# Debug-UART.net
KiCad netlist of a schematic drawn in Altium Designer
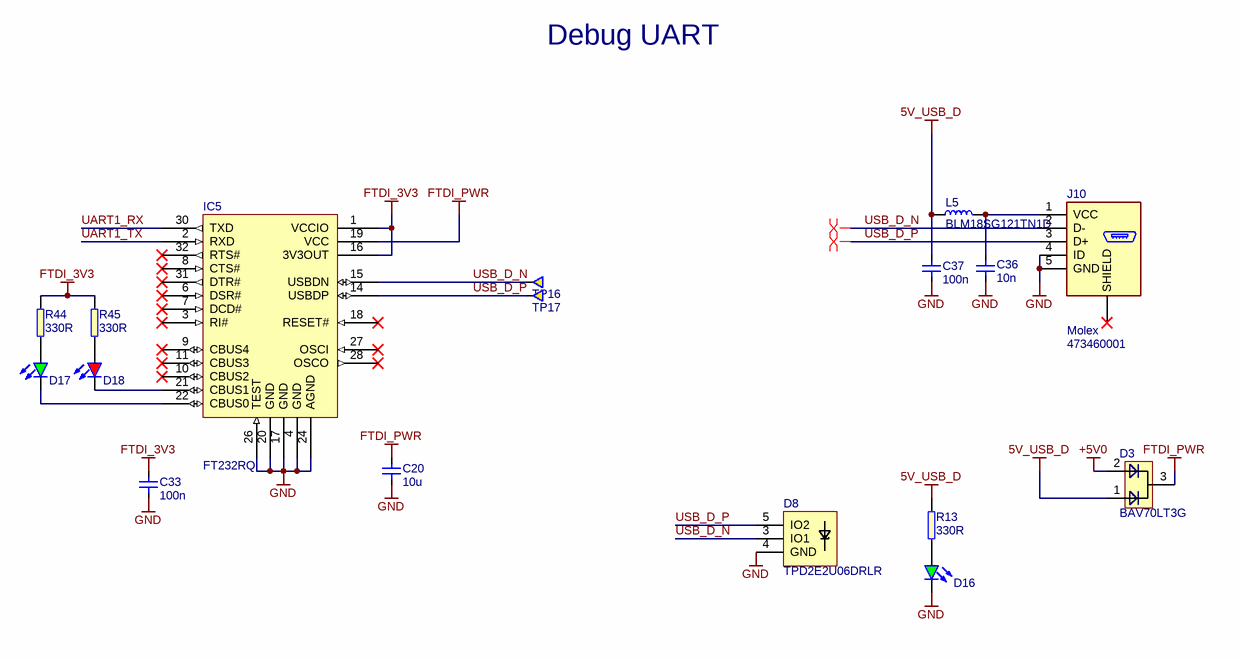
[diagram p0: Debug-UART.SchDoc]

(export (version "E")
  (design (tool "Eeschema 10.0.6"))
  (components
    (comp (ref "C20")
      (value "10u")
      (footprint "0402")
      (description "MLCC SMT Capacitor 10uF 0402")
      (fields (field (name "MANUFACTURER") "TDK") (field (name "PART NUMBER") "C_10u_0402"))
      (libsource (lib "TK1Baseboard") (part "C_10u_0402"))
    )
    (comp (ref "C33")
      (value "100n")
      (footprint "0402")
      (description "MLCC SMT Capacitor 100n 0402")
      (fields (field (name "MANUFACTURER") "TDK") (field (name "PART NUMBER") "C_100n_0402"))
      (libsource (lib "TK1Baseboard") (part "C_100n_0402"))
    )
    (comp (ref "C36")
      (value "10n")
      (footprint "0402")
      (description "MLCC SMT Capacitor 10 nF 0402")
      (fields (field (name "MANUFACTURER") "AVX") (field (name "PART NUMBER") "C_10n_0402"))
      (libsource (lib "TK1Baseboard") (part "C_10n_0402"))
    )
    (comp (ref "C37")
      (value "100n")
      (footprint "0402")
      (description "MLCC SMT Capacitor 100n 0402")
      (fields (field (name "MANUFACTURER") "TDK") (field (name "PART NUMBER") "C_100n_0402"))
      (libsource (lib "TK1Baseboard") (part "C_100n_0402"))
    )
    (comp (ref "D3")
      (value "BAV70LT3G")
      (footprint "SOT-23")
      (description "Dual switching diode, common cathode")
      (fields (field (name "MANUFACTURER") "ON SEMICONDUCTOR"))
      (libsource (lib "TK1Baseboard") (part "BAV70LT3G"))
    )
    (comp (ref "D8")
      (value "TPD2E2U06DRLR")
      (footprint "TPD2E2U06DRLR")
      (description "ESD Suppressors 2-CH")
      (fields (field (name "PART NUMBER") "TPD2E2U06") (field (name "MANUFACTURER") "Texas Instruments"))
      (libsource (lib "TK1Baseboard") (part "TPD2E2U06"))
    )
    (comp (ref "D16")
      (value "KPT-1608SGC")
      (footprint "LED0603")
      (description "LED Green 0603 case")
      (fields (field (name "PART NUMBER") "LED_G") (field (name "MANUFACTURER") "KINGBRIGHT"))
      (libsource (lib "TK1Baseboard") (part "LED_G"))
    )
    (comp (ref "D17")
      (value "KPT-1608SGC")
      (footprint "LED0603")
      (description "LED Green 0603 case")
      (fields (field (name "PART NUMBER") "LED_G") (field (name "MANUFACTURER") "KINGBRIGHT"))
      (libsource (lib "TK1Baseboard") (part "LED_G"))
    )
    (comp (ref "D18")
      (value "KPT-1608EC")
      (footprint "LED0603")
      (description "LED Red 0603 case")
      (fields (field (name "PART NUMBER") "LED_R") (field (name "MANUFACTURER") "KINGBRIGHT"))
      (libsource (lib "TK1Baseboard") (part "LED_R"))
    )
    (comp (ref "IC5")
      (value "FT232RQ")
      (footprint "QFN-32")
      (description "USB to serial UART interface")
      (fields (field (name "MANUFACTURER") "FTDI") (field (name "MPN") "FT232RQ-REEL"))
      (libsource (lib "TK1Baseboard") (part "FT232RQ"))
    )
    (comp (ref "J10")
      (value "Molex 47346-0001")
      (footprint "CON-Molex-047346-0001")
      (description "USB - micro B Receptacle Connector 5 Position Surface Mount, Right Angle, Horizontal")
      (fields
        (field (name "PART NUMBER") "CON-Molex-47346-0001")
        (field (name "MANUFACTURER") "Molex")
        (field (name "PART SYMBOL") "473460001")
        (field (name "MPN") "473460001")
      )
      (libsource (lib "TK1Baseboard") (part "Micro USB B"))
    )
    (comp (ref "L5")
      (value "BLM18SG121TN1D")
      (footprint "0603")
      (description "FERRITE BEAD, 0.025OHM, 3A, 0603")
      (fields (field (name "MANUFACTURER") "MURATA"))
      (libsource (lib "TK1Baseboard") (part "BLM18SG121TN1D"))
    )
    (comp (ref "R13")
      (value "330R")
      (footprint "0402")
      (description "RES, 330R, 0402")
      (fields (field (name "MANUFACTURER") "MULTICOMP") (field (name "PART NUMBER") "R_330R_0402"))
      (libsource (lib "TK1Baseboard") (part "R_330R_0402"))
    )
    (comp (ref "R44")
      (value "330R")
      (footprint "0402")
      (description "RES, 330R, 0402")
      (fields (field (name "MANUFACTURER") "MULTICOMP") (field (name "PART NUMBER") "R_330R_0402"))
      (libsource (lib "") (part "R_330R_0402_1"))
    )
    (comp (ref "R45")
      (value "330R")
      (footprint "0402")
      (description "RES, 330R, 0402")
      (fields (field (name "MANUFACTURER") "MULTICOMP") (field (name "PART NUMBER") "R_330R_0402"))
      (libsource (lib "") (part "R_330R_0402_1"))
    )
    (comp (ref "TP16")
      (value "TP-R-1.5")
      (footprint "TP-R-1.5")
      (description "Testpad, round, 1.5mm")
      (libsource (lib "TK1Baseboard") (part "TP-R-1.5"))
    )
    (comp (ref "TP17")
      (value "TP-R-1.5")
      (footprint "TP-R-1.5")
      (description "Testpad, round, 1.5mm")
      (libsource (lib "TK1Baseboard") (part "TP-R-1.5"))
    )
  )
  (nets
    (net (code "1") (name "+5V0") (class "Default")
      (node (ref "D3") (pin "2") (pinfunction "2_2") (pintype "passive"))
    )
    (net (code "2") (name "/UART1_RX") (class "Default")
      (node (ref "IC5") (pin "30") (pinfunction "TXD_30") (pintype "output"))
    )
    (net (code "3") (name "/UART1_TX") (class "Default")
      (node (ref "IC5") (pin "2") (pinfunction "RXD_2") (pintype "input"))
    )
    (net (code "4") (name "/USB_D_N") (class "Default")
      (node (ref "D8") (pin "3") (pinfunction "IO1_3") (pintype "passive"))
      (node (ref "IC5") (pin "15") (pinfunction "USBDN_15") (pintype "bidirectional"))
      (node (ref "J10") (pin "2") (pinfunction "D-_2") (pintype "passive"))
      (node (ref "TP16") (pin "1") (pintype "passive"))
    )
    (net (code "5") (name "/USB_D_P") (class "Default")
      (node (ref "D8") (pin "5") (pinfunction "IO2_5") (pintype "passive"))
      (node (ref "IC5") (pin "14") (pinfunction "USBDP_14") (pintype "bidirectional"))
      (node (ref "J10") (pin "3") (pinfunction "D+_3") (pintype "passive"))
      (node (ref "TP17") (pin "1") (pintype "passive"))
    )
    (net (code "6") (name "5V_USB_D") (class "Default")
      (node (ref "C37") (pin "2") (pinfunction "2_2") (pintype "passive"))
      (node (ref "D3") (pin "1") (pinfunction "1_1") (pintype "passive"))
      (node (ref "L5") (pin "1") (pintype "passive"))
      (node (ref "R13") (pin "2") (pintype "passive"))
    )
    (net (code "7") (name "FTDI_3V3") (class "Default")
      (node (ref "C33") (pin "2") (pinfunction "2_2") (pintype "passive"))
      (node (ref "IC5") (pin "1") (pinfunction "VCCIO_1") (pintype "power_in"))
      (node (ref "IC5") (pin "16") (pinfunction "3V3OUT_16") (pintype "power_in"))
      (node (ref "R44") (pin "2") (pintype "passive"))
      (node (ref "R45") (pin "2") (pintype "passive"))
    )
    (net (code "8") (name "FTDI_PWR") (class "Default")
      (node (ref "C20") (pin "2") (pinfunction "2_2") (pintype "passive"))
      (node (ref "D3") (pin "3") (pinfunction "3_3") (pintype "passive"))
      (node (ref "IC5") (pin "19") (pinfunction "VCC_19") (pintype "power_in"))
    )
    (net (code "9") (name "GND") (class "Default")
      (node (ref "C20") (pin "1") (pinfunction "1_1") (pintype "passive"))
      (node (ref "C33") (pin "1") (pinfunction "1_1") (pintype "passive"))
      (node (ref "C36") (pin "2") (pinfunction "2_2") (pintype "passive"))
      (node (ref "C37") (pin "1") (pinfunction "1_1") (pintype "passive"))
      (node (ref "D16") (pin "K") (pinfunction "K_K") (pintype "passive"))
      (node (ref "D8") (pin "4") (pinfunction "GND_4") (pintype "passive"))
      (node (ref "IC5") (pin "17") (pinfunction "GND_17") (pintype "power_in"))
      (node (ref "IC5") (pin "20") (pinfunction "GND_20") (pintype "power_in"))
      (node (ref "IC5") (pin "24") (pinfunction "AGND_24") (pintype "power_in"))
      (node (ref "IC5") (pin "26") (pinfunction "TEST_26") (pintype "input"))
      (node (ref "IC5") (pin "4") (pinfunction "GND_4") (pintype "power_in"))
      (node (ref "J10") (pin "4") (pinfunction "ID_4") (pintype "passive"))
      (node (ref "J10") (pin "5") (pinfunction "GND_5") (pintype "power_in"))
    )
    (net (code "10") (name "Net-(D16-PadA)") (class "Default")
      (node (ref "D16") (pin "A") (pinfunction "A_A") (pintype "passive"))
      (node (ref "R13") (pin "1") (pintype "passive"))
    )
    (net (code "11") (name "Net-(D17-PadA)") (class "Default")
      (node (ref "D17") (pin "A") (pinfunction "A_A") (pintype "passive"))
      (node (ref "R44") (pin "1") (pintype "passive"))
    )
    (net (code "12") (name "Net-(D18-PadA)") (class "Default")
      (node (ref "D18") (pin "A") (pinfunction "A_A") (pintype "passive"))
      (node (ref "R45") (pin "1") (pintype "passive"))
    )
    (net (code "13") (name "Net-(IC5-CBUS0)") (class "Default")
      (node (ref "D17") (pin "K") (pinfunction "K_K") (pintype "passive"))
      (node (ref "IC5") (pin "22") (pinfunction "CBUS0_22") (pintype "bidirectional"))
    )
    (net (code "14") (name "Net-(IC5-CBUS1)") (class "Default")
      (node (ref "D18") (pin "K") (pinfunction "K_K") (pintype "passive"))
      (node (ref "IC5") (pin "21") (pinfunction "CBUS1_21") (pintype "bidirectional"))
    )
    (net (code "15") (name "Net-(J10-VCC)") (class "Default")
      (node (ref "C36") (pin "1") (pinfunction "1_1") (pintype "passive"))
      (node (ref "J10") (pin "1") (pinfunction "VCC_1") (pintype "power_in"))
      (node (ref "L5") (pin "2") (pintype "passive"))
    )
    (net (code "16") (name "unconnected-(IC5-CBUS2-Pad10)") (class "Default")
      (node (ref "IC5") (pin "10") (pinfunction "CBUS2_10") (pintype "bidirectional+no_connect"))
    )
    (net (code "17") (name "unconnected-(IC5-CBUS3-Pad11)") (class "Default")
      (node (ref "IC5") (pin "11") (pinfunction "CBUS3_11") (pintype "bidirectional+no_connect"))
    )
    (net (code "18") (name "unconnected-(IC5-CBUS4-Pad9)") (class "Default")
      (node (ref "IC5") (pin "9") (pinfunction "CBUS4_9") (pintype "bidirectional+no_connect"))
    )
    (net (code "19") (name "unconnected-(IC5-CTS#-Pad8)") (class "Default")
      (node (ref "IC5") (pin "8") (pinfunction "CTS#_8") (pintype "input+no_connect"))
    )
    (net (code "20") (name "unconnected-(IC5-DCD#-Pad7)") (class "Default")
      (node (ref "IC5") (pin "7") (pinfunction "DCD#_7") (pintype "input+no_connect"))
    )
    (net (code "21") (name "unconnected-(IC5-DSR#-Pad6)") (class "Default")
      (node (ref "IC5") (pin "6") (pinfunction "DSR#_6") (pintype "input+no_connect"))
    )
    (net (code "22") (name "unconnected-(IC5-DTR#-Pad31)") (class "Default")
      (node (ref "IC5") (pin "31") (pinfunction "DTR#_31") (pintype "output+no_connect"))
    )
    (net (code "23") (name "unconnected-(IC5-OSCI-Pad27)") (class "Default")
      (node (ref "IC5") (pin "27") (pinfunction "OSCI_27") (pintype "input+no_connect"))
    )
    (net (code "24") (name "unconnected-(IC5-OSCO-Pad28)") (class "Default")
      (node (ref "IC5") (pin "28") (pinfunction "OSCO_28") (pintype "output+no_connect"))
    )
    (net (code "25") (name "unconnected-(IC5-RESET#-Pad18)") (class "Default")
      (node (ref "IC5") (pin "18") (pinfunction "RESET#_18") (pintype "input+no_connect"))
    )
    (net (code "26") (name "unconnected-(IC5-RI#-Pad3)") (class "Default")
      (node (ref "IC5") (pin "3") (pinfunction "RI#_3") (pintype "input+no_connect"))
    )
    (net (code "27") (name "unconnected-(IC5-RTS#-Pad32)") (class "Default")
      (node (ref "IC5") (pin "32") (pinfunction "RTS#_32") (pintype "output+no_connect"))
    )
    (net (code "28") (name "unconnected-(J10-SHIELD-PadS)") (class "Default")
      (node (ref "J10") (pin "S") (pinfunction "SHIELD_S") (pintype "passive+no_connect"))
    )
  )
)
